# LPDA_2_SMA.net
KiCad netlist of a schematic drawn in Altium Designer
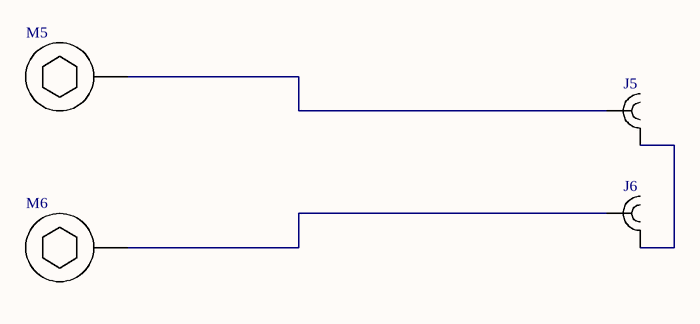
[diagram p0: LPDA_2_SMA.SchDoc]

(export (version "E")
  (design (tool "Eeschema 10.0.6"))
  (components
    (comp (ref "J5")
      (value "CONSMA001-G")
      (footprint "SMA TH Vertical Linx CONSMA001-G")
      (description "SMA TH VERTICAL LINX CONSMA001-G")
      (libsource (lib "Connector") (part "SMA TH VERTICAL LINX CONSMA001-G"))
    )
    (comp (ref "J6")
      (value "CONSMA001-G")
      (footprint "SMA TH Vertical Linx CONSMA001-G")
      (description "SMA TH VERTICAL LINX CONSMA001-G")
      (libsource (lib "Connector") (part "SMA TH VERTICAL LINX CONSMA001-G"))
    )
    (comp (ref "M5")
      (value "~")
      (footprint "Screw Hex Socket M2.5X4 Connected")
      (description "Screw Hex Socket Connected BN610")
      (libsource (lib "Mechanic") (part "Screw Hex Socket Connected"))
    )
    (comp (ref "M6")
      (value "~")
      (footprint "Screw Hex Socket M2.5X4 Connected")
      (description "Screw Hex Socket Connected BN610")
      (libsource (lib "Mechanic") (part "Screw Hex Socket Connected"))
    )
  )
  (nets
    (net (code "1") (name "Net-(J5-Pad1)") (class "Default")
      (node (ref "J5") (pin "1") (pinfunction "1_1") (pintype "passive"))
      (node (ref "M5") (pin "1") (pinfunction "1_1") (pintype "passive"))
    )
    (net (code "2") (name "Net-(J5-Pad2)") (class "Default")
      (node (ref "J5") (pin "2") (pinfunction "2_2") (pintype "passive"))
      (node (ref "J6") (pin "2") (pinfunction "2_2") (pintype "passive"))
    )
    (net (code "3") (name "Net-(J6-Pad1)") (class "Default")
      (node (ref "J6") (pin "1") (pinfunction "1_1") (pintype "passive"))
      (node (ref "M6") (pin "1") (pinfunction "1_1") (pintype "passive"))
    )
  )
)
